# wetl.net
KiCad netlist of a schematic drawn in EAGLE
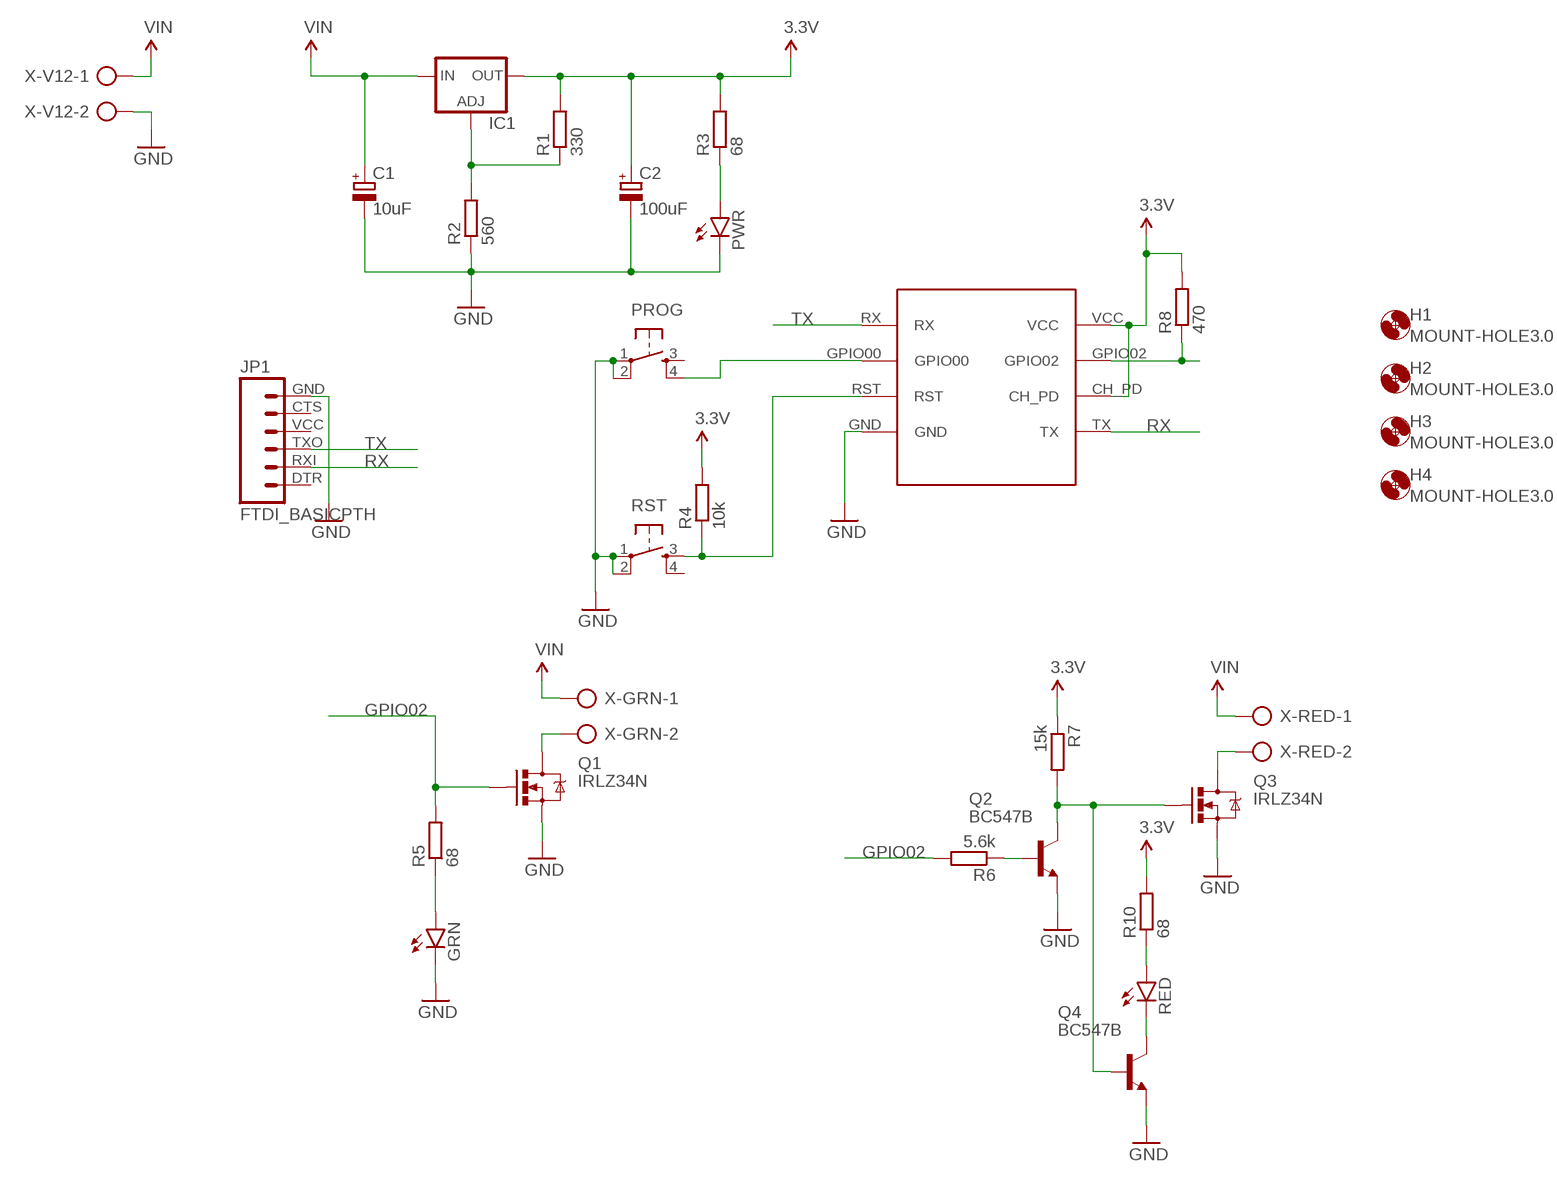
[diagram p0: schematic, sheet 1]

(export (version "E")
  (design (tool "Eeschema 10.0.6"))
  (components
    (comp (ref "C1")
      (value "10uF")
      (footprint "eagle-import:E2,5-6")
      (libsource (lib "eagle-import") (part "CPOL-EUE2.5-6"))
    )
    (comp (ref "C2")
      (value "100uF")
      (footprint "eagle-import:E2,5-6")
      (libsource (lib "eagle-import") (part "CPOL-EUE2.5-6"))
    )
    (comp (ref "GRN")
      (value "LED5MM")
      (footprint "eagle-import:LED5MM")
      (libsource (lib "eagle-import") (part "LED5MM"))
    )
    (comp (ref "H1")
      (value "MOUNT-HOLE3.0")
      (footprint "eagle-import:3,0")
      (libsource (lib "eagle-import") (part "MOUNT-HOLE3.0"))
    )
    (comp (ref "H2")
      (value "MOUNT-HOLE3.0")
      (footprint "eagle-import:3,0")
      (libsource (lib "eagle-import") (part "MOUNT-HOLE3.0"))
    )
    (comp (ref "H3")
      (value "MOUNT-HOLE3.0")
      (footprint "eagle-import:3,0")
      (libsource (lib "eagle-import") (part "MOUNT-HOLE3.0"))
    )
    (comp (ref "H4")
      (value "MOUNT-HOLE3.0")
      (footprint "eagle-import:3,0")
      (libsource (lib "eagle-import") (part "MOUNT-HOLE3.0"))
    )
    (comp (ref "IC1")
      (value "LM317TS")
      (footprint "eagle-import:317TS")
      (libsource (lib "eagle-import") (part "LM317TS"))
    )
    (comp (ref "JP1")
      (value "FTDI_BASICPTH")
      (footprint "eagle-import:FTDI_BASIC")
      (libsource (lib "eagle-import") (part "FTDI_BASICPTH"))
    )
    (comp (ref "PROG")
      (value "TAC_SWITCHPTH")
      (footprint "eagle-import:TACTILE-PTH")
      (libsource (lib "eagle-import") (part "TAC_SWITCHPTH"))
    )
    (comp (ref "PWR")
      (value "LED5MM")
      (footprint "eagle-import:LED5MM")
      (libsource (lib "eagle-import") (part "LED5MM"))
    )
    (comp (ref "Q1")
      (value "IRLZ34N")
      (footprint "eagle-import:TO220V")
      (libsource (lib "eagle-import") (part "MOSFET-NCHANNELFQP30N06L"))
    )
    (comp (ref "Q2")
      (value "BC547B")
      (footprint "eagle-import:TO92")
      (libsource (lib "eagle-import") (part "BC547B"))
    )
    (comp (ref "Q3")
      (value "IRLZ34N")
      (footprint "eagle-import:TO220V")
      (libsource (lib "eagle-import") (part "MOSFET-NCHANNELFQP30N06L"))
    )
    (comp (ref "Q4")
      (value "BC547B")
      (footprint "eagle-import:TO92")
      (libsource (lib "eagle-import") (part "BC547B"))
    )
    (comp (ref "R1")
      (value "330")
      (footprint "eagle-import:0204V")
      (libsource (lib "eagle-import") (part "R-EU_0204/2V"))
    )
    (comp (ref "R2")
      (value "560")
      (footprint "eagle-import:0204V")
      (libsource (lib "eagle-import") (part "R-EU_0204/2V"))
    )
    (comp (ref "R3")
      (value "68")
      (footprint "eagle-import:0204V")
      (libsource (lib "eagle-import") (part "R-EU_0204/2V"))
    )
    (comp (ref "R4")
      (value "10k")
      (footprint "eagle-import:0204_7")
      (libsource (lib "eagle-import") (part "R-EU_0204/7"))
    )
    (comp (ref "R5")
      (value "68")
      (footprint "eagle-import:0204V")
      (libsource (lib "eagle-import") (part "R-EU_0204/2V"))
    )
    (comp (ref "R6")
      (value "5.6k")
      (footprint "eagle-import:0204V")
      (libsource (lib "eagle-import") (part "R-EU_0204/2V"))
    )
    (comp (ref "R7")
      (value "15k")
      (footprint "eagle-import:0204V")
      (libsource (lib "eagle-import") (part "R-EU_0204/2V"))
    )
    (comp (ref "R8")
      (value "470")
      (footprint "eagle-import:0204_7")
      (libsource (lib "eagle-import") (part "R-EU_0204/7"))
    )
    (comp (ref "R10")
      (value "68")
      (footprint "eagle-import:0204V")
      (libsource (lib "eagle-import") (part "R-EU_0204/2V"))
    )
    (comp (ref "RED")
      (value "LED5MM")
      (footprint "eagle-import:LED5MM")
      (libsource (lib "eagle-import") (part "LED5MM"))
    )
    (comp (ref "RST")
      (value "TAC_SWITCHPTH")
      (footprint "eagle-import:TACTILE-PTH")
      (libsource (lib "eagle-import") (part "TAC_SWITCHPTH"))
    )
    (comp (ref "U$2")
      (value "ESP8266")
      (footprint "eagle-import:ESP-01")
      (libsource (lib "eagle-import") (part "ESP8266"))
    )
    (comp (ref "X-GRN")
      (value "SMKDSP_1,5/2")
      (footprint "eagle-import:SMKDSP_1,5_2")
      (fields (field (name "MF") "FARNELL") (field (name "MPN") "1733570"))
      (libsource (lib "eagle-import") (part "SMKDSP_1,5/2"))
    )
    (comp (ref "X-RED")
      (value "SMKDSP_1,5/2")
      (footprint "eagle-import:SMKDSP_1,5_2")
      (fields (field (name "MF") "FARNELL") (field (name "MPN") "1733570"))
      (libsource (lib "eagle-import") (part "SMKDSP_1,5/2"))
    )
    (comp (ref "X-V12")
      (value "SMKDSP_1,5/2")
      (footprint "eagle-import:SMKDSP_1,5_2")
      (fields (field (name "MF") "FARNELL") (field (name "MPN") "1733570"))
      (libsource (lib "eagle-import") (part "SMKDSP_1,5/2"))
    )
  )
  (nets
    (net (code "1") (name "/GPIO02") (class "Default")
      (node (ref "Q1") (pin "1") (pinfunction "G_1") (pintype "passive"))
      (node (ref "R5") (pin "2") (pinfunction "2_2") (pintype "passive"))
      (node (ref "R6") (pin "2") (pinfunction "2_2") (pintype "passive"))
      (node (ref "R8") (pin "1") (pinfunction "1_1") (pintype "passive"))
      (node (ref "U$2") (pin "GPIO02") (pinfunction "GPIO02_GPIO02") (pintype "bidirectional"))
    )
    (net (code "2") (name "/RX") (class "Default")
      (node (ref "JP1") (pin "RXI") (pinfunction "2_RXI") (pintype "passive"))
      (node (ref "U$2") (pin "TX") (pinfunction "TX_TX") (pintype "bidirectional"))
    )
    (net (code "3") (name "/TX") (class "Default")
      (node (ref "JP1") (pin "TXO") (pinfunction "3_TXO") (pintype "passive"))
      (node (ref "U$2") (pin "RX") (pinfunction "RX_RX") (pintype "bidirectional"))
    )
    (net (code "4") (name "3.3V") (class "Default")
      (node (ref "C2") (pin "+") (pinfunction "+_+") (pintype "passive"))
      (node (ref "IC1") (pin "2") (pinfunction "OUT_2") (pintype "passive"))
      (node (ref "R1") (pin "2") (pinfunction "2_2") (pintype "passive"))
      (node (ref "R10") (pin "2") (pinfunction "2_2") (pintype "passive"))
      (node (ref "R3") (pin "2") (pinfunction "2_2") (pintype "passive"))
      (node (ref "R4") (pin "2") (pinfunction "2_2") (pintype "passive"))
      (node (ref "R7") (pin "1") (pinfunction "1_1") (pintype "passive"))
      (node (ref "R8") (pin "2") (pinfunction "2_2") (pintype "passive"))
      (node (ref "U$2") (pin "CH_PD") (pinfunction "CH_PD_CH_PD") (pintype "bidirectional"))
      (node (ref "U$2") (pin "VCC") (pinfunction "VCC_VCC") (pintype "bidirectional"))
    )
    (net (code "5") (name "GND") (class "Default")
      (node (ref "C1") (pin "-") (pinfunction "-_-") (pintype "passive"))
      (node (ref "C2") (pin "-") (pinfunction "-_-") (pintype "passive"))
      (node (ref "GRN") (pin "K") (pinfunction "C_K") (pintype "passive"))
      (node (ref "JP1") (pin "GND") (pinfunction "6_GND") (pintype "passive"))
      (node (ref "PROG") (pin "1") (pinfunction "1_1") (pintype "passive"))
      (node (ref "PROG") (pin "2") (pinfunction "2_2") (pintype "passive"))
      (node (ref "PWR") (pin "K") (pinfunction "C_K") (pintype "passive"))
      (node (ref "Q1") (pin "3") (pinfunction "S_3") (pintype "passive"))
      (node (ref "Q2") (pin "1") (pinfunction "E_1") (pintype "passive"))
      (node (ref "Q3") (pin "3") (pinfunction "S_3") (pintype "passive"))
      (node (ref "Q4") (pin "1") (pinfunction "E_1") (pintype "passive"))
      (node (ref "R2") (pin "1") (pinfunction "1_1") (pintype "passive"))
      (node (ref "RST") (pin "1") (pinfunction "1_1") (pintype "passive"))
      (node (ref "RST") (pin "2") (pinfunction "2_2") (pintype "passive"))
      (node (ref "U$2") (pin "GND") (pinfunction "GND_GND") (pintype "bidirectional"))
      (node (ref "X-V12") (pin "2") (pinfunction "KL_2") (pintype "passive"))
    )
    (net (code "6") (name "Net-(GRN-PadA)") (class "Default")
      (node (ref "GRN") (pin "A") (pinfunction "A_A") (pintype "passive"))
      (node (ref "R5") (pin "1") (pinfunction "1_1") (pintype "passive"))
    )
    (net (code "7") (name "Net-(IC1-ADJ)") (class "Default")
      (node (ref "IC1") (pin "1") (pinfunction "ADJ_1") (pintype "input"))
      (node (ref "R1") (pin "1") (pinfunction "1_1") (pintype "passive"))
      (node (ref "R2") (pin "2") (pinfunction "2_2") (pintype "passive"))
    )
    (net (code "8") (name "Net-(PROG-Pad4)") (class "Default")
      (node (ref "PROG") (pin "4") (pinfunction "4_4") (pintype "passive"))
      (node (ref "U$2") (pin "GPIO00") (pinfunction "GPIO00_GPIO00") (pintype "bidirectional"))
    )
    (net (code "9") (name "Net-(PWR-PadA)") (class "Default")
      (node (ref "PWR") (pin "A") (pinfunction "A_A") (pintype "passive"))
      (node (ref "R3") (pin "1") (pinfunction "1_1") (pintype "passive"))
    )
    (net (code "10") (name "Net-(Q1-D)") (class "Default")
      (node (ref "Q1") (pin "2") (pinfunction "D_2") (pintype "passive"))
      (node (ref "X-GRN") (pin "2") (pinfunction "KL_2") (pintype "passive"))
    )
    (net (code "11") (name "Net-(Q2-B)") (class "Default")
      (node (ref "Q2") (pin "2") (pinfunction "B_2") (pintype "passive"))
      (node (ref "R6") (pin "1") (pinfunction "1_1") (pintype "passive"))
    )
    (net (code "12") (name "Net-(Q2-C)") (class "Default")
      (node (ref "Q2") (pin "3") (pinfunction "C_3") (pintype "passive"))
      (node (ref "Q3") (pin "1") (pinfunction "G_1") (pintype "passive"))
      (node (ref "Q4") (pin "2") (pinfunction "B_2") (pintype "passive"))
      (node (ref "R7") (pin "2") (pinfunction "2_2") (pintype "passive"))
    )
    (net (code "13") (name "Net-(Q3-D)") (class "Default")
      (node (ref "Q3") (pin "2") (pinfunction "D_2") (pintype "passive"))
      (node (ref "X-RED") (pin "2") (pinfunction "KL_2") (pintype "passive"))
    )
    (net (code "14") (name "Net-(Q4-C)") (class "Default")
      (node (ref "Q4") (pin "3") (pinfunction "C_3") (pintype "passive"))
      (node (ref "RED") (pin "K") (pinfunction "C_K") (pintype "passive"))
    )
    (net (code "15") (name "Net-(R4-Pad1)") (class "Default")
      (node (ref "R4") (pin "1") (pinfunction "1_1") (pintype "passive"))
      (node (ref "RST") (pin "3") (pinfunction "3_3") (pintype "passive"))
      (node (ref "U$2") (pin "RST") (pinfunction "RST_RST") (pintype "bidirectional"))
    )
    (net (code "16") (name "Net-(R10-Pad1)") (class "Default")
      (node (ref "R10") (pin "1") (pinfunction "1_1") (pintype "passive"))
      (node (ref "RED") (pin "A") (pinfunction "A_A") (pintype "passive"))
    )
    (net (code "17") (name "VIN") (class "Default")
      (node (ref "C1") (pin "+") (pinfunction "+_+") (pintype "passive"))
      (node (ref "IC1") (pin "3") (pinfunction "IN_3") (pintype "input"))
      (node (ref "X-GRN") (pin "1") (pinfunction "KL_1") (pintype "passive"))
      (node (ref "X-RED") (pin "1") (pinfunction "KL_1") (pintype "passive"))
      (node (ref "X-V12") (pin "1") (pinfunction "KL_1") (pintype "passive"))
    )
    (net (code "18") (name "unconnected-(JP1-1-PadDTR)") (class "Default")
      (node (ref "JP1") (pin "DTR") (pinfunction "1_DTR") (pintype "passive"))
    )
    (net (code "19") (name "unconnected-(JP1-4-PadVCC)") (class "Default")
      (node (ref "JP1") (pin "VCC") (pinfunction "4_VCC") (pintype "passive"))
    )
    (net (code "20") (name "unconnected-(JP1-5-PadCTS)") (class "Default")
      (node (ref "JP1") (pin "CTS") (pinfunction "5_CTS") (pintype "passive"))
    )
    (net (code "21") (name "unconnected-(PROG-Pad3)") (class "Default")
      (node (ref "PROG") (pin "3") (pinfunction "3_3") (pintype "passive"))
    )
    (net (code "22") (name "unconnected-(RST-Pad4)") (class "Default")
      (node (ref "RST") (pin "4") (pinfunction "4_4") (pintype "passive"))
    )
  )
)
